# charging-module.net
KiCad netlist of a schematic drawn in Altium Designer
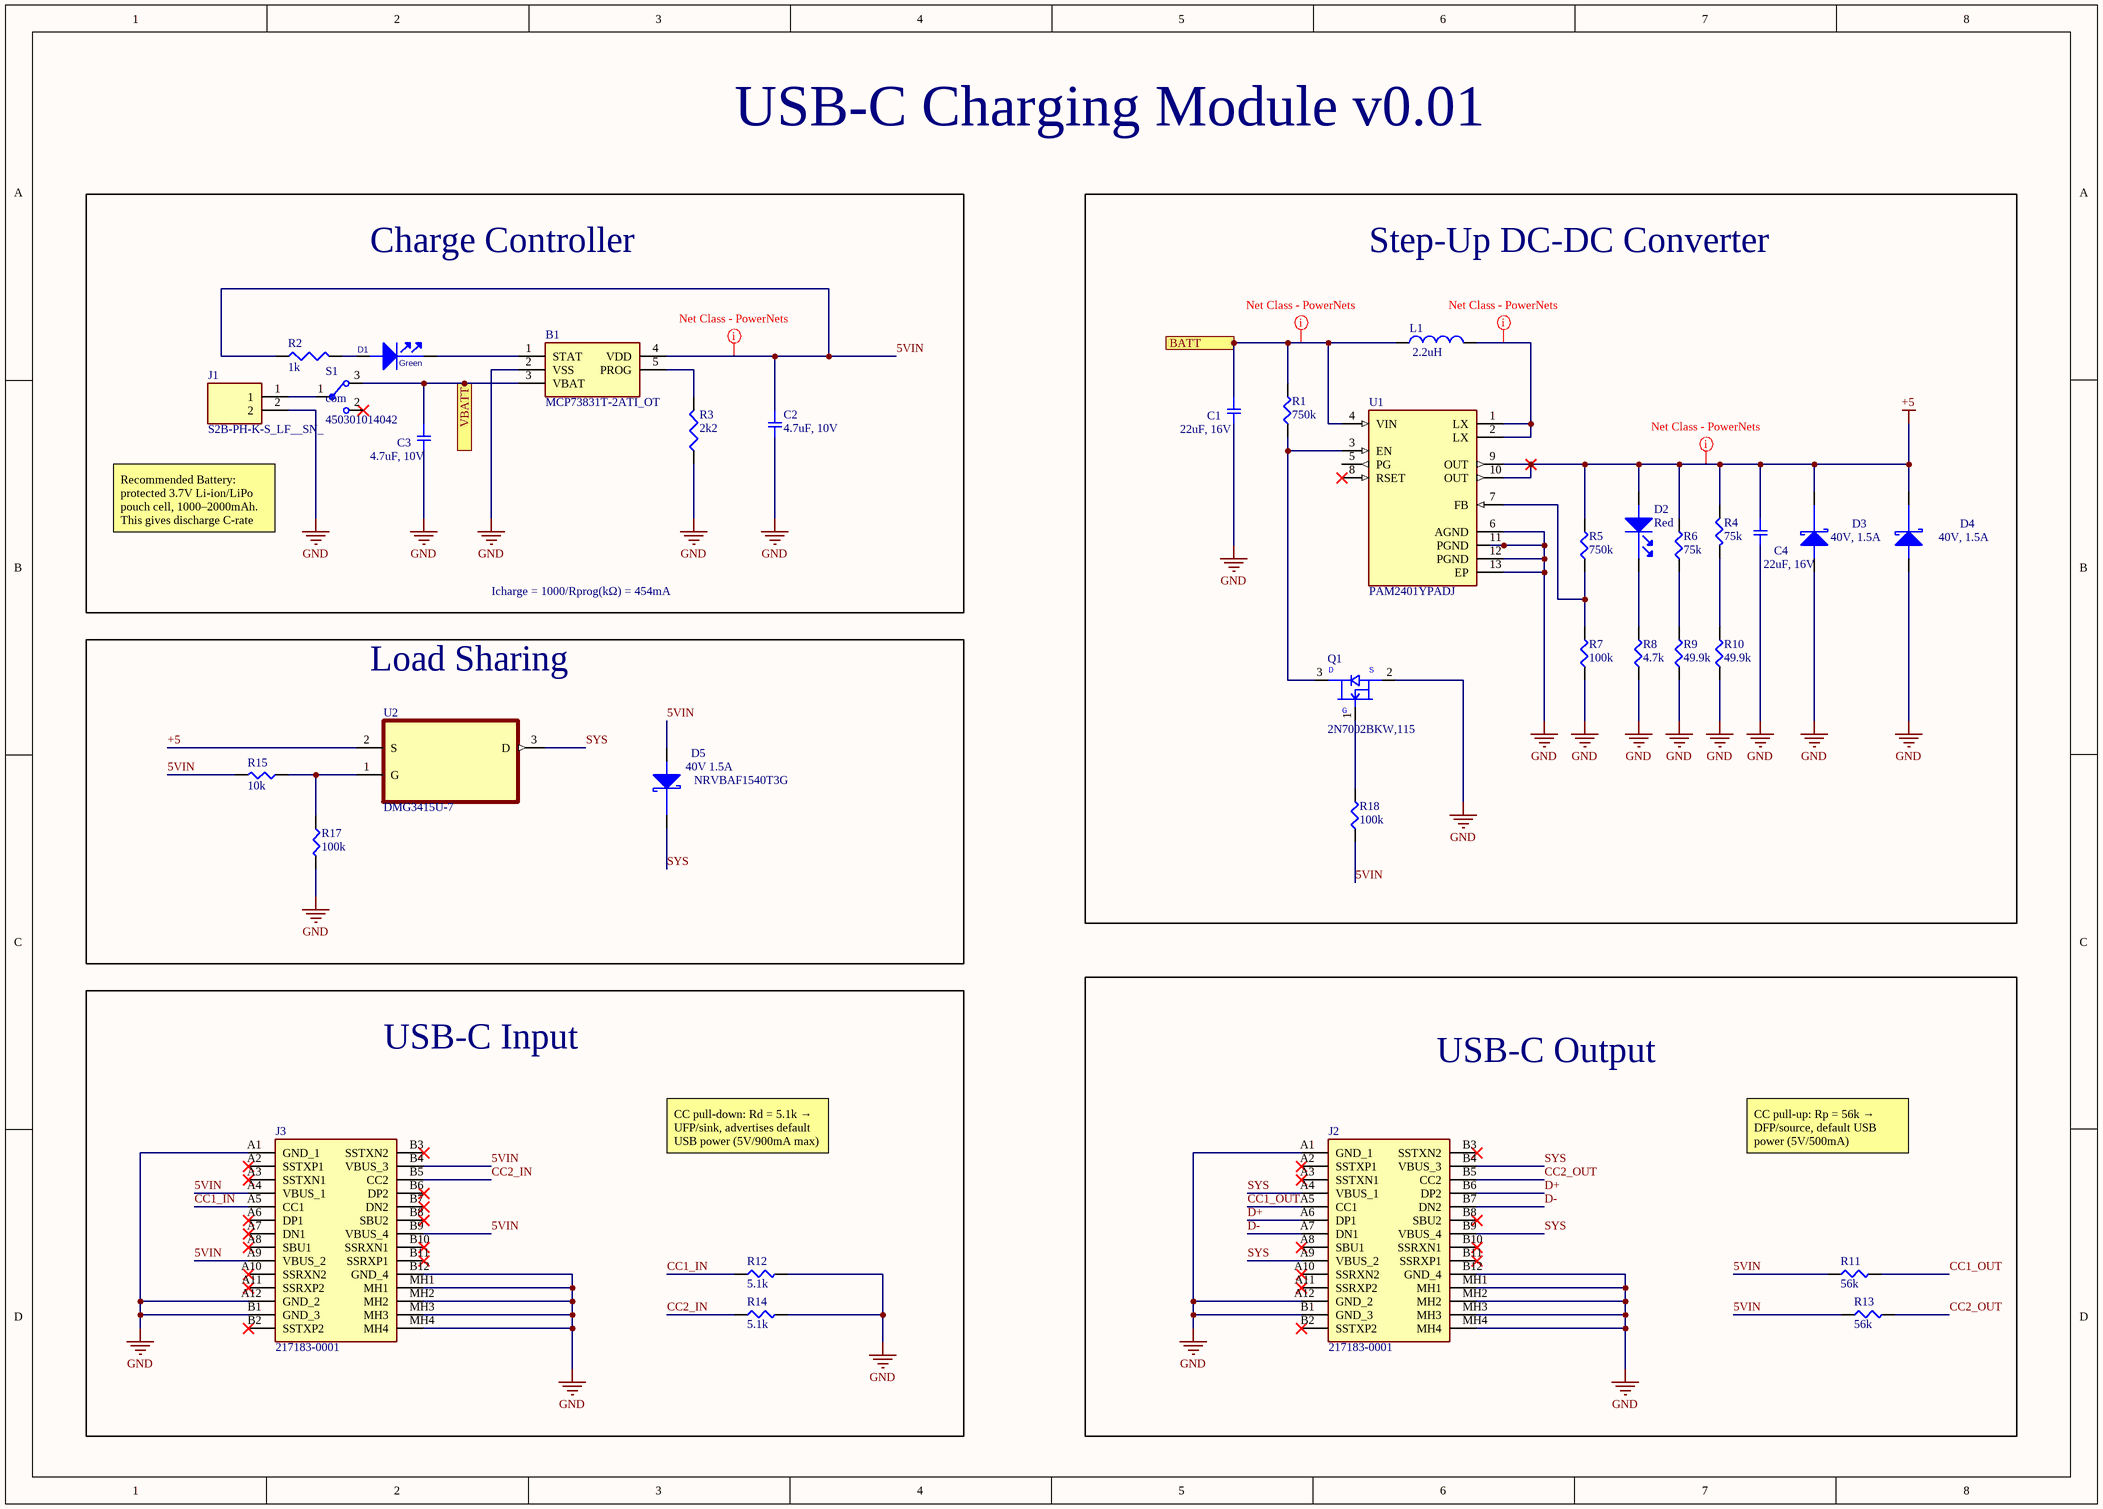
[diagram p0: charging-module.SchDoc]

(export (version "E")
  (design (tool "Eeschema 10.0.6"))
  (components
    (comp (ref "B1")
      (value "MCP73831T-2ATI_OT")
      (footprint "SOT95P270X145-5N")
      (description "Microchip MCP73831T-2ATI/OT, Battery Charge Controller Lithium-Ion/Polymer, 500mA, 5-pin SOT-23")
      (fields
        (field (name "MANUFACTURER_PART_NUMBER") "MCP73831T-2ATI/OT")
        (field (name "MOUSER PART NUMBER") "579-MCP73831T-2ATIOT")
      )
      (libsource (lib "MCP73831T-2ATI_OT") (part "MCP73831T-2ATI_OT"))
    )
    (comp (ref "C1")
      (value "22uF, 16V")
      (footprint "SMD-1206C")
      (description "CAP CER 22UF 16V X5R 1206")
      (fields
        (field (name "DIGI-KEY PART NUMBER") "490-12763-1-ND")
        (field (name "PART NUMBER") "GRM319R61C226ME15D")
      )
      (libsource (lib "CAP123") (part "GRM319R61C226ME15D"))
    )
    (comp (ref "C2")
      (value "4.7uF, 10V")
      (footprint "SMD-0603C")
      (description "CAP CER 4.7UF 10V X5R 0603")
      (fields
        (field (name "DIGI-KEY PART NUMBER") "490-10478-1-ND")
        (field (name "PART NUMBER") "GRM188R61A475ME15D")
      )
      (libsource (lib "capacitor_murata_0603") (part "GRM188R61A475ME15D"))
    )
    (comp (ref "C3")
      (value "4.7uF, 10V")
      (footprint "SMD-0603C")
      (description "CAP CER 4.7UF 10V X5R 0603")
      (fields
        (field (name "DIGI-KEY PART NUMBER") "490-10478-1-ND")
        (field (name "PART NUMBER") "GRM188R61A475ME15D")
      )
      (libsource (lib "capacitor_murata_0603") (part "GRM188R61A475ME15D"))
    )
    (comp (ref "C4")
      (value "22uF, 16V")
      (footprint "SMD-1206C")
      (description "CAP CER 22UF 16V X5R 1206")
      (fields
        (field (name "DIGI-KEY PART NUMBER") "490-12763-1-ND")
        (field (name "PART NUMBER") "GRM319R61C226ME15D")
      )
      (libsource (lib "CAP123") (part "GRM319R61C226ME15D"))
    )
    (comp (ref "D1")
      (value "Green")
      (footprint "LED_0603")
      (description "LED SMARTLED GREEN 570NM 0603")
      (fields
        (field (name "MANUFACTURER") "OSRAM Opto Semiconductors Inc")
        (field (name "MANUFACTURER PART NUMBER") "LG L29K-G2J1-24-Z")
      )
      (libsource (lib "iMX6 Rex Development Baseboard V1I1") (part "LG L29K-G2J1-24-Z"))
    )
    (comp (ref "D2")
      (value "Red")
      (footprint "LED_0603")
      (description "LED SMARTLED RED 630NM 0603 SMD")
      (fields
        (field (name "MANUFACTURER") "OSRAM Opto Semiconductors Inc")
        (field (name "MANUFACTURER PART NUMBER") "LS L29K-H1J2-1-Z")
        (field (name ".CHECKED PCB") "RF")
        (field (name ".CHECKED SCH") "RF")
      )
      (libsource (lib "iMX6 Rex Development Baseboard V1I1") (part "LS L29K-H1J2-1-Z"))
    )
    (comp (ref "D3")
      (value "40V, 1.5A")
      (footprint "SMC")
      (description "Rectifier Diode Schottky Si 40V 1.5A Automotive T/R / Surface Mount Schottky Power Rectifier")
      (fields
        (field (name "MANUFACTURER") "onsemi")
        (field (name "MANUFACTURER PART NUMBER") "NRVBAF1540T3G")
      )
      (libsource (lib "iMX6 Rex Development Baseboard V1I1") (part "B560C-13-F"))
    )
    (comp (ref "D4")
      (value "40V, 1.5A")
      (footprint "SMC")
      (description "Rectifier Diode Schottky Si 40V 1.5A Automotive T/R / Surface Mount Schottky Power Rectifier")
      (fields
        (field (name "MANUFACTURER") "onsemi")
        (field (name "MANUFACTURER PART NUMBER") "NRVBAF1540T3G")
      )
      (libsource (lib "iMX6 Rex Development Baseboard V1I1") (part "B560C-13-F"))
    )
    (comp (ref "D5")
      (value "40V 1.5A")
      (footprint "SMC")
      (description "Rectifier Diode Schottky Si 40V 1.5A Automotive T/R / Surface Mount Schottky Power Rectifier")
      (fields
        (field (name "SUPPLIER PART NUMBER 1") "NRVBAF1540T3G")
        (field (name "MANUFACTURER") "onsemi")
        (field (name "MANUFACTURER PART NUMBER") "NRVBAF1540T3G")
      )
      (libsource (lib "iMX6 Rex Development Baseboard V1I1") (part "B560C-13-F"))
    )
    (comp (ref "J1")
      (value "S2B-PH-K-S_LF__SN_")
      (footprint "SHDRRA2W50P0X200_1X2_590X760X480P")
      (fields
        (field (name "MANUFACTURER_PART_NUMBER") "S2B-PH-K-S(LF)(SN)")
        (field (name "MOUSER PART NUMBER") "306-S2BPHKSLFSNPP")
      )
      (libsource (lib "S2B-PH-K-S_LF__SN_") (part "S2B-PH-K-S_LF__SN_"))
    )
    (comp (ref "J2")
      (value "217183-0001")
      (footprint "2171830001")
      (description "Connector USB Type C Hybrid Female 24Positions 0.5mm Right Angle Through Hole Embossed T/R")
      (fields (field (name "MOUSER PART NUMBER") "538-217183-0001"))
      (libsource (lib "217183-0001") (part "217183-0001"))
    )
    (comp (ref "J3")
      (value "217183-0001")
      (footprint "2171830001")
      (description "Connector USB Type C Hybrid Female 24Positions 0.5mm Right Angle Through Hole Embossed T/R")
      (fields (field (name "MOUSER PART NUMBER") "538-217183-0001"))
      (libsource (lib "217183-0001") (part "217183-0001"))
    )
    (comp (ref "L1")
      (value "2.2uH")
      (footprint "INDPM7265X300N")
      (description "Inductor Power Shielded Wirewound 2.2uH 20% 1MHz Metal 6.8A 0.0193Ohm DCR T/R")
      (fields
        (field (name "MANUFACTURER") "Sumida")
        (field (name "MANUFACTURER PART NUMBER") "CDMC6D28NP-2R2MC")
      )
      (libsource (lib "Miscellaneous Devices") (part "Inductor"))
    )
    (comp (ref "Q1")
      (value "2N7002BKW,115")
      (footprint "SC70_SOT323")
      (description "MOSFET N-CH 60V 310MA SOT323")
      (fields
        (field (name "MANUFACTURER") "NXP Semiconductors")
        (field (name ".CHECKED PCB") "RF")
        (field (name ".CHECKED SCH") "RF")
      )
      (libsource (lib "iMX6 Rex Development Baseboard V1I1") (part "2N7002BKW,115"))
    )
    (comp (ref "R1")
      (value "750k")
      (footprint "SMD-0402-RES")
      (description "RES SMD 750K OHM 1% 1/10W 0402")
      (fields
        (field (name "PART NUMBER") "ERJ-2RKF7503X")
        (field (name "DIGI-KEY PART NUMBER") "P750KLCT-ND")
      )
      (libsource (lib "Panasonic_ERJ_0402") (part "ERJ-2RKF7503X"))
    )
    (comp (ref "R2")
      (value "1k")
      (footprint "R0402")
      (description "RES 1.00K OHM 1/16W 1% 0402 SMD")
      (fields
        (field (name "MANUFACTURER") "Yageo")
        (field (name "MANUFACTURER PART NUMBER") "RC0402FR-071KL")
      )
      (libsource (lib "iMX6 Rex Development Baseboard V1I1") (part "RC0402FR-071KL"))
    )
    (comp (ref "R3")
      (value "2k2")
      (footprint "R0402")
      (description "RES 2.20K OHM 1/16W 1% 0402 SMD")
      (fields
        (field (name "MANUFACTURER") "Yageo")
        (field (name "MANUFACTURER PART NUMBER") "RC0402FR-072K2L")
      )
      (libsource (lib "iMX6 Rex Development Baseboard V1I1") (part "RC0402FR-072K2L"))
    )
    (comp (ref "R4")
      (value "75k")
      (footprint "SMD-0603-RES")
      (description "RES SMD 75K OHM 1% 1/10W 0603")
      (fields
        (field (name "PART NUMBER") "ERJ-3EKF7502V")
        (field (name "DIGI-KEY PART NUMBER") "P75.0KHCT-ND")
      )
      (libsource (lib "Panasonic_ERJ_0603") (part "ERJ-3EKF7502V"))
    )
    (comp (ref "R5")
      (value "750k")
      (footprint "SMD-0402-RES")
      (description "RES SMD 750K OHM 1% 1/10W 0402")
      (fields
        (field (name "PART NUMBER") "ERJ-2RKF7503X")
        (field (name "DIGI-KEY PART NUMBER") "P750KLCT-ND")
      )
      (libsource (lib "Panasonic_ERJ_0402") (part "ERJ-2RKF7503X"))
    )
    (comp (ref "R6")
      (value "75k")
      (footprint "SMD-0603-RES")
      (description "RES SMD 75K OHM 1% 1/10W 0603")
      (fields
        (field (name "PART NUMBER") "ERJ-3EKF7502V")
        (field (name "DIGI-KEY PART NUMBER") "P75.0KHCT-ND")
      )
      (libsource (lib "Panasonic_ERJ_0603") (part "ERJ-3EKF7502V"))
    )
    (comp (ref "R7")
      (value "100k")
      (footprint "SMD-0603-RES")
      (description "RES SMD 100K OHM 1% 1/10W 0603")
      (fields
        (field (name "PART NUMBER") "ERJ-3EKF1003V")
        (field (name "DIGI-KEY PART NUMBER") "P100KHCT-ND")
      )
      (libsource (lib "Panasonic_ERJ_0603") (part "ERJ-3EKF1003V"))
    )
    (comp (ref "R8")
      (value "4.7k")
      (footprint "SMD-0603-RES")
      (description "RES SMD 4.7K OHM 1% 1/10W 0603")
      (fields
        (field (name "PART NUMBER") "ERJ-3EKF4701V")
        (field (name "DIGI-KEY PART NUMBER") "P4.70KHCT-ND")
      )
      (libsource (lib "Panasonic_ERJ_0603") (part "ERJ-3EKF4701V"))
    )
    (comp (ref "R9")
      (value "49.9k")
      (footprint "SMD-0603-RES")
      (description "RES SMD 49.9K OHM 1% 1/10W 0603")
      (fields
        (field (name "PART NUMBER") "ERJ-3EKF4992V")
        (field (name "DIGI-KEY PART NUMBER") "P49.9KHCT-ND")
      )
      (libsource (lib "Panasonic_ERJ_0603") (part "ERJ-3EKF4992V"))
    )
    (comp (ref "R10")
      (value "49.9k")
      (footprint "SMD-0603-RES")
      (description "RES SMD 49.9K OHM 1% 1/10W 0603")
      (fields
        (field (name "PART NUMBER") "ERJ-3EKF4992V")
        (field (name "DIGI-KEY PART NUMBER") "P49.9KHCT-ND")
      )
      (libsource (lib "Panasonic_ERJ_0603") (part "ERJ-3EKF4992V"))
    )
    (comp (ref "R11")
      (value "56k")
      (footprint "SMD-0402-RES")
      (description "RES SMD 56K OHM 5% 1/10W 0402")
      (fields (field (name "PART NUMBER") "ERJ-2GEJ563X") (field (name "DIGI-KEY PART NUMBER") "P56KJCT-ND"))
      (libsource (lib "Panasonic_ERJ_0402") (part "ERJ-2GEJ563X"))
    )
    (comp (ref "R12")
      (value "5.1k")
      (footprint "R0402")
      (description "RES SMD 5.1K OHM 1% 1/4W 1206")
      (fields
        (field (name "PART NUMBER") "ERJ-8ENF5101V")
        (field (name "DIGI-KEY PART NUMBER") "P5.10KFCT-ND")
      )
      (libsource (lib "Panasonic_ERJ_1206") (part "ERJ-8ENF5101V"))
    )
    (comp (ref "R13")
      (value "56k")
      (footprint "SMD-0402-RES")
      (description "RES SMD 56K OHM 5% 1/10W 0402")
      (fields (field (name "PART NUMBER") "ERJ-2GEJ563X") (field (name "DIGI-KEY PART NUMBER") "P56KJCT-ND"))
      (libsource (lib "Panasonic_ERJ_0402") (part "ERJ-2GEJ563X"))
    )
    (comp (ref "R14")
      (value "5.1k")
      (footprint "iMX6 Rex_V1I1:R0402")
      (description "RES SMD 5.1K OHM 1% 1/4W 1206")
      (fields
        (field (name "PART NUMBER") "ERJ-8ENF5101V")
        (field (name "DIGI-KEY PART NUMBER") "P5.10KFCT-ND")
      )
      (libsource (lib "Panasonic_ERJ_1206") (part "ERJ-8ENF5101V"))
    )
    (comp (ref "R15")
      (value "10k")
      (footprint "SMD-0201-RES")
      (description "RES SMD 10K OHM 1% 1/20W 0201")
      (fields
        (field (name "PART NUMBER") "ERJ-1GEF1002C")
        (field (name "DIGI-KEY PART NUMBER") "P10.0KABCT-ND")
      )
      (libsource (lib "Panasonic_ERJ_0201") (part "ERJ-1GEF1002C"))
    )
    (comp (ref "R17")
      (value "100k")
      (footprint "SMD-0603-RES")
      (description "RES SMD 100K OHM 1% 1/10W 0603")
      (fields
        (field (name "PART NUMBER") "ERJ-3EKF1003V")
        (field (name "DIGI-KEY PART NUMBER") "P100KHCT-ND")
      )
      (libsource (lib "Panasonic_ERJ_0603") (part "ERJ-3EKF1003V"))
    )
    (comp (ref "R18")
      (value "100k")
      (footprint "SMD-0603-RES")
      (description "RES SMD 100K OHM 1% 1/10W 0603")
      (fields
        (field (name "PART NUMBER") "ERJ-3EKF1003V")
        (field (name "DIGI-KEY PART NUMBER") "P100KHCT-ND")
      )
      (libsource (lib "Panasonic_ERJ_0603") (part "ERJ-3EKF1003V"))
    )
    (comp (ref "S1")
      (value "450301014042")
      (footprint "450301014042")
      (fields (field (name "MF") "{'manufacturer': u'~{W}xfcrth Elektronik'}"))
      (libsource (lib "450301014042") (part "450301014042"))
    )
    (comp (ref "U1")
      (value "PAM2401YPADJ")
      (footprint "SON45P300X300X63-13N")
      (description "Conv DC-DC 0.9V to 4.75V Synchronous Step Up Single-Out 2.5V to 5V 12-Pin UDFN EP T/R")
      (fields (field (name "MANUFACTURER") "Diodes Inc."))
      (libsource (lib "PAM2401YPADJ") (part "PAM2401YPADJ"))
    )
    (comp (ref "U2")
      (value "DMG3415U-7")
      (footprint "SOT95P240X105-3N")
      (description "P-ch Mosfet 20V 4A 39MΩ@4A, 4.5V 9.1NC@4.5V 294PF@10V SOT-23-3 SMD 2.9MM × 1.3MM × 1.03MM")
      (fields (field (name "MANUFACTURER") "Diodes Inc."))
      (libsource (lib "DMG3415U-7") (part "DMG3415U-7"))
    )
  )
  (nets
    (net (code "1") (name "+5") (class "Default")
      (node (ref "C4") (pin "1") (pinfunction "1_1") (pintype "passive"))
      (node (ref "D2") (pin "2") (pinfunction "ANODE_2") (pintype "passive"))
      (node (ref "D3") (pin "1") (pinfunction "cathode_1") (pintype "passive"))
      (node (ref "D4") (pin "1") (pinfunction "cathode_1") (pintype "passive"))
      (node (ref "R4") (pin "1") (pinfunction "1_1") (pintype "passive"))
      (node (ref "R5") (pin "2") (pinfunction "2_2") (pintype "passive"))
      (node (ref "R6") (pin "2") (pinfunction "2_2") (pintype "passive"))
      (node (ref "U1") (pin "10") (pinfunction "OUT_10") (pintype "output"))
      (node (ref "U1") (pin "9") (pinfunction "OUT_9") (pintype "output"))
      (node (ref "U2") (pin "2") (pinfunction "S_2") (pintype "passive"))
    )
    (net (code "2") (name "/5VIN") (class "Default")
      (node (ref "B1") (pin "4") (pinfunction "VDD_4") (pintype "passive"))
      (node (ref "C2") (pin "1") (pinfunction "1_1") (pintype "passive"))
      (node (ref "D5") (pin "2") (pinfunction "ANODE_2") (pintype "passive"))
      (node (ref "J3") (pin "A4") (pinfunction "VBUS_1_A4") (pintype "passive"))
      (node (ref "J3") (pin "A9") (pinfunction "VBUS_2_A9") (pintype "passive"))
      (node (ref "J3") (pin "B4") (pinfunction "VBUS_3_B4") (pintype "passive"))
      (node (ref "J3") (pin "B9") (pinfunction "VBUS_4_B9") (pintype "passive"))
      (node (ref "R11") (pin "1") (pinfunction "1_1") (pintype "passive"))
      (node (ref "R13") (pin "1") (pinfunction "1_1") (pintype "passive"))
      (node (ref "R15") (pin "2") (pinfunction "2_2") (pintype "passive"))
      (node (ref "R18") (pin "1") (pinfunction "1_1") (pintype "passive"))
      (node (ref "R2") (pin "1") (pinfunction "1_1") (pintype "passive"))
    )
    (net (code "3") (name "/BATT") (class "Default")
      (node (ref "C1") (pin "1") (pinfunction "1_1") (pintype "passive"))
      (node (ref "L1") (pin "1") (pinfunction "1_1") (pintype "passive"))
      (node (ref "R1") (pin "2") (pinfunction "2_2") (pintype "passive"))
      (node (ref "U1") (pin "4") (pinfunction "VIN_4") (pintype "input"))
    )
    (net (code "4") (name "/CC1_IN") (class "Default")
      (node (ref "J3") (pin "A5") (pinfunction "CC1_A5") (pintype "passive"))
      (node (ref "R12") (pin "1") (pinfunction "1_1") (pintype "passive"))
    )
    (net (code "5") (name "/CC1_OUT") (class "Default")
      (node (ref "J2") (pin "A5") (pinfunction "CC1_A5") (pintype "passive"))
      (node (ref "R11") (pin "2") (pinfunction "2_2") (pintype "passive"))
    )
    (net (code "6") (name "/CC2_IN") (class "Default")
      (node (ref "J3") (pin "B5") (pinfunction "CC2_B5") (pintype "passive"))
      (node (ref "R14") (pin "1") (pinfunction "1_1") (pintype "passive"))
    )
    (net (code "7") (name "/CC2_OUT") (class "Default")
      (node (ref "J2") (pin "B5") (pinfunction "CC2_B5") (pintype "passive"))
      (node (ref "R13") (pin "2") (pinfunction "2_2") (pintype "passive"))
    )
    (net (code "8") (name "/D+") (class "Default")
      (node (ref "J2") (pin "A6") (pinfunction "DP1_A6") (pintype "passive"))
      (node (ref "J2") (pin "B6") (pinfunction "DP2_B6") (pintype "passive"))
    )
    (net (code "9") (name "/D-") (class "Default")
      (node (ref "J2") (pin "A7") (pinfunction "DN1_A7") (pintype "passive"))
      (node (ref "J2") (pin "B7") (pinfunction "DN2_B7") (pintype "passive"))
    )
    (net (code "10") (name "/SYS") (class "Default")
      (node (ref "D5") (pin "1") (pinfunction "cathode_1") (pintype "passive"))
      (node (ref "J2") (pin "A4") (pinfunction "VBUS_1_A4") (pintype "passive"))
      (node (ref "J2") (pin "A9") (pinfunction "VBUS_2_A9") (pintype "passive"))
      (node (ref "J2") (pin "B4") (pinfunction "VBUS_3_B4") (pintype "passive"))
      (node (ref "J2") (pin "B9") (pinfunction "VBUS_4_B9") (pintype "passive"))
      (node (ref "U2") (pin "3") (pinfunction "D_3") (pintype "output"))
    )
    (net (code "11") (name "/VBATT") (class "Default")
      (node (ref "B1") (pin "3") (pinfunction "VBAT_3") (pintype "passive"))
      (node (ref "C3") (pin "1") (pinfunction "1_1") (pintype "passive"))
      (node (ref "S1") (pin "3") (pinfunction "3_3") (pintype "passive"))
    )
    (net (code "12") (name "GND") (class "Default")
      (node (ref "B1") (pin "2") (pinfunction "VSS_2") (pintype "passive"))
      (node (ref "C1") (pin "2") (pinfunction "2_2") (pintype "passive"))
      (node (ref "C2") (pin "2") (pinfunction "2_2") (pintype "passive"))
      (node (ref "C3") (pin "2") (pinfunction "2_2") (pintype "passive"))
      (node (ref "C4") (pin "2") (pinfunction "2_2") (pintype "passive"))
      (node (ref "D3") (pin "2") (pinfunction "ANODE_2") (pintype "passive"))
      (node (ref "D4") (pin "2") (pinfunction "ANODE_2") (pintype "passive"))
      (node (ref "J1") (pin "2") (pinfunction "2_2") (pintype "passive"))
      (node (ref "J2") (pin "A1") (pinfunction "GND_1_A1") (pintype "passive"))
      (node (ref "J2") (pin "A12") (pinfunction "GND_2_A12") (pintype "passive"))
      (node (ref "J2") (pin "B1") (pinfunction "GND_3_B1") (pintype "passive"))
      (node (ref "J2") (pin "B12") (pinfunction "GND_4_B12") (pintype "passive"))
      (node (ref "J2") (pin "MH1") (pinfunction "MH1_MH1") (pintype "passive"))
      (node (ref "J2") (pin "MH2") (pinfunction "MH2_MH2") (pintype "passive"))
      (node (ref "J2") (pin "MH3") (pinfunction "MH3_MH3") (pintype "passive"))
      (node (ref "J2") (pin "MH4") (pinfunction "MH4_MH4") (pintype "passive"))
      (node (ref "J3") (pin "A1") (pinfunction "GND_1_A1") (pintype "passive"))
      (node (ref "J3") (pin "A12") (pinfunction "GND_2_A12") (pintype "passive"))
      (node (ref "J3") (pin "B1") (pinfunction "GND_3_B1") (pintype "passive"))
      (node (ref "J3") (pin "B12") (pinfunction "GND_4_B12") (pintype "passive"))
      (node (ref "J3") (pin "MH1") (pinfunction "MH1_MH1") (pintype "passive"))
      (node (ref "J3") (pin "MH2") (pinfunction "MH2_MH2") (pintype "passive"))
      (node (ref "J3") (pin "MH3") (pinfunction "MH3_MH3") (pintype "passive"))
      (node (ref "J3") (pin "MH4") (pinfunction "MH4_MH4") (pintype "passive"))
      (node (ref "Q1") (pin "2") (pinfunction "SOURCE_2") (pintype "passive"))
      (node (ref "R10") (pin "1") (pinfunction "1_1") (pintype "passive"))
      (node (ref "R12") (pin "2") (pinfunction "2_2") (pintype "passive"))
      (node (ref "R14") (pin "2") (pinfunction "2_2") (pintype "passive"))
      (node (ref "R17") (pin "2") (pinfunction "2_2") (pintype "passive"))
      (node (ref "R3") (pin "1") (pinfunction "1_1") (pintype "passive"))
      (node (ref "R7") (pin "1") (pinfunction "1_1") (pintype "passive"))
      (node (ref "R8") (pin "1") (pinfunction "1_1") (pintype "passive"))
      (node (ref "R9") (pin "1") (pinfunction "1_1") (pintype "passive"))
      (node (ref "U1") (pin "11") (pinfunction "PGND_11") (pintype "power_in"))
      (node (ref "U1") (pin "12") (pinfunction "PGND_12") (pintype "power_in"))
      (node (ref "U1") (pin "13") (pinfunction "EP_13") (pintype "power_in"))
      (node (ref "U1") (pin "6") (pinfunction "AGND_6") (pintype "power_in"))
    )
    (net (code "13") (name "Net-(B1-PROG)") (class "Default")
      (node (ref "B1") (pin "5") (pinfunction "PROG_5") (pintype "passive"))
      (node (ref "R3") (pin "2") (pinfunction "2_2") (pintype "passive"))
    )
    (net (code "14") (name "Net-(B1-STAT)") (class "Default")
      (node (ref "B1") (pin "1") (pinfunction "STAT_1") (pintype "passive"))
      (node (ref "D1") (pin "1") (pinfunction "cathode_1") (pintype "passive"))
    )
    (net (code "15") (name "Net-(D1-ANODE)") (class "Default")
      (node (ref "D1") (pin "2") (pinfunction "ANODE_2") (pintype "passive"))
      (node (ref "R2") (pin "2") (pinfunction "2_2") (pintype "passive"))
    )
    (net (code "16") (name "Net-(D2-cathode)") (class "Default")
      (node (ref "D2") (pin "1") (pinfunction "cathode_1") (pintype "passive"))
      (node (ref "R8") (pin "2") (pinfunction "2_2") (pintype "passive"))
    )
    (net (code "17") (name "Net-(J1-Pad1)") (class "Default")
      (node (ref "J1") (pin "1") (pinfunction "1_1") (pintype "passive"))
      (node (ref "S1") (pin "1") (pinfunction "1_1") (pintype "passive"))
    )
    (net (code "18") (name "Net-(L1-Pad2)") (class "Default")
      (node (ref "L1") (pin "2") (pinfunction "2_2") (pintype "passive"))
      (node (ref "U1") (pin "1") (pinfunction "LX_1") (pintype "passive"))
      (node (ref "U1") (pin "2") (pinfunction "LX_2") (pintype "passive"))
    )
    (net (code "19") (name "Net-(Q1-DRAIN)") (class "Default")
      (node (ref "Q1") (pin "3") (pinfunction "DRAIN_3") (pintype "passive"))
      (node (ref "R1") (pin "1") (pinfunction "1_1") (pintype "passive"))
      (node (ref "U1") (pin "3") (pinfunction "EN_3") (pintype "input"))
    )
    (net (code "20") (name "Net-(Q1-GATE)") (class "Default")
      (node (ref "Q1") (pin "1") (pinfunction "GATE_1") (pintype "passive"))
      (node (ref "R18") (pin "2") (pinfunction "2_2") (pintype "passive"))
    )
    (net (code "21") (name "Net-(R6-Pad1)") (class "Default")
      (node (ref "R6") (pin "1") (pinfunction "1_1") (pintype "passive"))
      (node (ref "R9") (pin "2") (pinfunction "2_2") (pintype "passive"))
    )
    (net (code "22") (name "Net-(R10-Pad2)") (class "Default")
      (node (ref "R10") (pin "2") (pinfunction "2_2") (pintype "passive"))
      (node (ref "R4") (pin "2") (pinfunction "2_2") (pintype "passive"))
    )
    (net (code "23") (name "Net-(U1-FB)") (class "Default")
      (node (ref "R5") (pin "1") (pinfunction "1_1") (pintype "passive"))
      (node (ref "R7") (pin "2") (pinfunction "2_2") (pintype "passive"))
      (node (ref "U1") (pin "7") (pinfunction "FB_7") (pintype "input"))
    )
    (net (code "24") (name "Net-(U2-G)") (class "Default")
      (node (ref "R15") (pin "1") (pinfunction "1_1") (pintype "passive"))
      (node (ref "R17") (pin "1") (pinfunction "1_1") (pintype "passive"))
      (node (ref "U2") (pin "1") (pinfunction "G_1") (pintype "power_in"))
    )
    (net (code "25") (name "unconnected-(J2-SBU1-PadA8)") (class "Default")
      (node (ref "J2") (pin "A8") (pinfunction "SBU1_A8") (pintype "passive+no_connect"))
    )
    (net (code "26") (name "unconnected-(J2-SBU2-PadB8)") (class "Default")
      (node (ref "J2") (pin "B8") (pinfunction "SBU2_B8") (pintype "passive+no_connect"))
    )
    (net (code "27") (name "unconnected-(J2-SSRXN1-PadB10)") (class "Default")
      (node (ref "J2") (pin "B10") (pinfunction "SSRXN1_B10") (pintype "passive+no_connect"))
    )
    (net (code "28") (name "unconnected-(J2-SSRXN2-PadA10)") (class "Default")
      (node (ref "J2") (pin "A10") (pinfunction "SSRXN2_A10") (pintype "passive+no_connect"))
    )
    (net (code "29") (name "unconnected-(J2-SSRXP1-PadB11)") (class "Default")
      (node (ref "J2") (pin "B11") (pinfunction "SSRXP1_B11") (pintype "passive+no_connect"))
    )
    (net (code "30") (name "unconnected-(J2-SSRXP2-PadA11)") (class "Default")
      (node (ref "J2") (pin "A11") (pinfunction "SSRXP2_A11") (pintype "passive+no_connect"))
    )
    (net (code "31") (name "unconnected-(J2-SSTXN1-PadA3)") (class "Default")
      (node (ref "J2") (pin "A3") (pinfunction "SSTXN1_A3") (pintype "passive+no_connect"))
    )
    (net (code "32") (name "unconnected-(J2-SSTXN2-PadB3)") (class "Default")
      (node (ref "J2") (pin "B3") (pinfunction "SSTXN2_B3") (pintype "passive+no_connect"))
    )
    (net (code "33") (name "unconnected-(J2-SSTXP1-PadA2)") (class "Default")
      (node (ref "J2") (pin "A2") (pinfunction "SSTXP1_A2") (pintype "passive+no_connect"))
    )
    (net (code "34") (name "unconnected-(J2-SSTXP2-PadB2)") (class "Default")
      (node (ref "J2") (pin "B2") (pinfunction "SSTXP2_B2") (pintype "passive+no_connect"))
    )
    (net (code "35") (name "unconnected-(J3-DN1-PadA7)") (class "Default")
      (node (ref "J3") (pin "A7") (pinfunction "DN1_A7") (pintype "passive+no_connect"))
    )
    (net (code "36") (name "unconnected-(J3-DN2-PadB7)") (class "Default")
      (node (ref "J3") (pin "B7") (pinfunction "DN2_B7") (pintype "passive+no_connect"))
    )
    (net (code "37") (name "unconnected-(J3-DP1-PadA6)") (class "Default")
      (node (ref "J3") (pin "A6") (pinfunction "DP1_A6") (pintype "passive+no_connect"))
    )
    (net (code "38") (name "unconnected-(J3-DP2-PadB6)") (class "Default")
      (node (ref "J3") (pin "B6") (pinfunction "DP2_B6") (pintype "passive+no_connect"))
    )
    (net (code "39") (name "unconnected-(J3-SBU1-PadA8)") (class "Default")
      (node (ref "J3") (pin "A8") (pinfunction "SBU1_A8") (pintype "passive+no_connect"))
    )
    (net (code "40") (name "unconnected-(J3-SBU2-PadB8)") (class "Default")
      (node (ref "J3") (pin "B8") (pinfunction "SBU2_B8") (pintype "passive+no_connect"))
    )
    (net (code "41") (name "unconnected-(J3-SSRXN1-PadB10)") (class "Default")
      (node (ref "J3") (pin "B10") (pinfunction "SSRXN1_B10") (pintype "passive+no_connect"))
    )
    (net (code "42") (name "unconnected-(J3-SSRXN2-PadA10)") (class "Default")
      (node (ref "J3") (pin "A10") (pinfunction "SSRXN2_A10") (pintype "passive+no_connect"))
    )
    (net (code "43") (name "unconnected-(J3-SSRXP1-PadB11)") (class "Default")
      (node (ref "J3") (pin "B11") (pinfunction "SSRXP1_B11") (pintype "passive+no_connect"))
    )
    (net (code "44") (name "unconnected-(J3-SSRXP2-PadA11)") (class "Default")
      (node (ref "J3") (pin "A11") (pinfunction "SSRXP2_A11") (pintype "passive+no_connect"))
    )
    (net (code "45") (name "unconnected-(J3-SSTXN1-PadA3)") (class "Default")
      (node (ref "J3") (pin "A3") (pinfunction "SSTXN1_A3") (pintype "passive+no_connect"))
    )
    (net (code "46") (name "unconnected-(J3-SSTXN2-PadB3)") (class "Default")
      (node (ref "J3") (pin "B3") (pinfunction "SSTXN2_B3") (pintype "passive+no_connect"))
    )
    (net (code "47") (name "unconnected-(J3-SSTXP1-PadA2)") (class "Default")
      (node (ref "J3") (pin "A2") (pinfunction "SSTXP1_A2") (pintype "passive+no_connect"))
    )
    (net (code "48") (name "unconnected-(J3-SSTXP2-PadB2)") (class "Default")
      (node (ref "J3") (pin "B2") (pinfunction "SSTXP2_B2") (pintype "passive+no_connect"))
    )
    (net (code "49") (name "unconnected-(S1-Pad2)") (class "Default")
      (node (ref "S1") (pin "2") (pinfunction "2_2") (pintype "passive+no_connect"))
    )
    (net (code "50") (name "unconnected-(U1-PG-Pad5)") (class "Default")
      (node (ref "U1") (pin "5") (pinfunction "PG_5") (pintype "output"))
    )
    (net (code "51") (name "unconnected-(U1-RSET-Pad8)") (class "Default")
      (node (ref "U1") (pin "8") (pinfunction "RSET_8") (pintype "input+no_connect"))
    )
  )
)
